# e3_tp1_ej1.net
KiCad netlist of a schematic drawn in Altium Designer
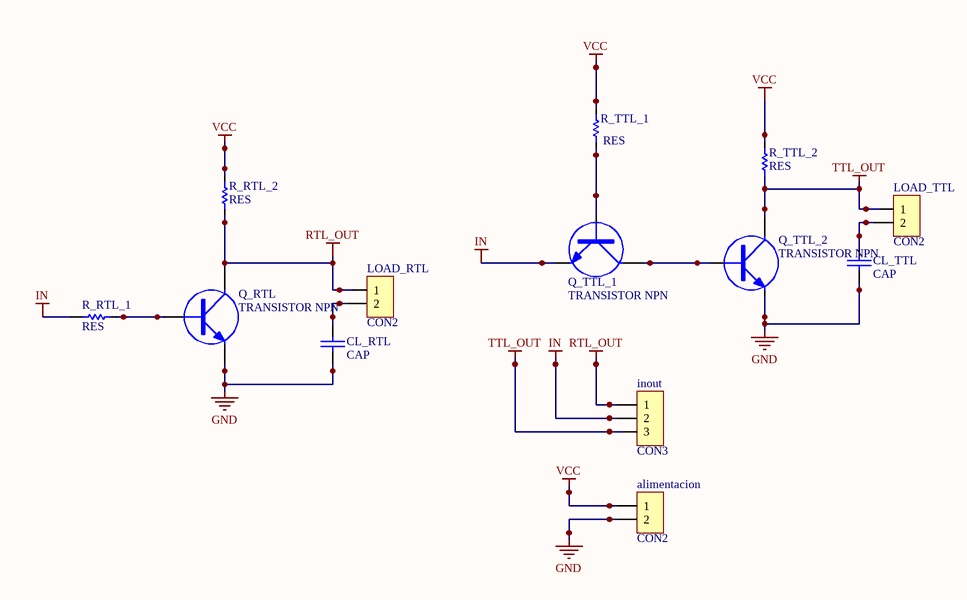
[diagram p0: e3_tp1_ej1.SchDoc]

(export (version "E")
  (design (tool "Eeschema 10.0.6"))
  (components
    (comp (ref "alimentacion") (value "CON2") (footprint "SIP2") (libsource (lib "LIBEBAL") (part "CON2")))
    (comp (ref "CL_RTL") (value "CAP") (footprint "CAP200") (libsource (lib "LIBEBAL") (part "CAP")))
    (comp (ref "CL_TTL") (value "CAP") (footprint "CAP200") (libsource (lib "LIBEBAL") (part "CAP")))
    (comp (ref "inout") (value "CON3") (footprint "SIP3") (libsource (lib "LIBEBAL") (part "CON3")))
    (comp (ref "LOAD_RTL") (value "CON2") (footprint "SIP2") (libsource (lib "LIBEBAL") (part "CON2")))
    (comp (ref "LOAD_TTL") (value "CON2") (footprint "SIP2") (libsource (lib "LIBEBAL") (part "CON2")))
    (comp (ref "Q_RTL")
      (value "TRANSISTOR NPN")
      (footprint "TO92")
      (libsource (lib "LIBEBAL") (part "TRANSISTOR NPN"))
    )
    (comp (ref "Q_TTL_1")
      (value "TRANSISTOR NPN")
      (footprint "TO92")
      (libsource (lib "LIBEBAL") (part "TRANSISTOR NPN"))
    )
    (comp (ref "Q_TTL_2")
      (value "TRANSISTOR NPN")
      (footprint "TO92")
      (libsource (lib "LIBEBAL") (part "TRANSISTOR NPN"))
    )
    (comp (ref "R_RTL_1") (value "RES") (footprint "RES300") (libsource (lib "LIBEBAL") (part "RES")))
    (comp (ref "R_RTL_2") (value "RES") (footprint "RES300") (libsource (lib "LIBEBAL") (part "RES")))
    (comp (ref "R_TTL_1") (value "RES") (footprint "RES300") (libsource (lib "LIBEBAL") (part "RES")))
    (comp (ref "R_TTL_2") (value "RES") (footprint "RES300") (libsource (lib "LIBEBAL") (part "RES")))
  )
  (nets
    (net (code "1") (name "GND") (class "Default")
      (node (ref "CL_RTL") (pin "2") (pinfunction "2_2") (pintype "passive"))
      (node (ref "CL_TTL") (pin "2") (pinfunction "2_2") (pintype "passive"))
      (node (ref "Q_RTL") (pin "3") (pinfunction "E_3") (pintype "passive"))
      (node (ref "Q_TTL_2") (pin "3") (pinfunction "E_3") (pintype "passive"))
      (node (ref "alimentacion") (pin "2") (pinfunction "2_2") (pintype "passive"))
    )
    (net (code "2") (name "IN") (class "Default")
      (node (ref "Q_TTL_1") (pin "3") (pinfunction "E_3") (pintype "passive"))
      (node (ref "R_RTL_1") (pin "1") (pinfunction "1_1") (pintype "passive"))
      (node (ref "inout") (pin "2") (pinfunction "2_2") (pintype "passive"))
    )
    (net (code "3") (name "Net-(CL_RTL-Pad1)") (class "Default")
      (node (ref "CL_RTL") (pin "1") (pinfunction "1_1") (pintype "passive"))
      (node (ref "LOAD_RTL") (pin "2") (pinfunction "2_2") (pintype "passive"))
    )
    (net (code "4") (name "Net-(CL_TTL-Pad1)") (class "Default")
      (node (ref "CL_TTL") (pin "1") (pinfunction "1_1") (pintype "passive"))
      (node (ref "LOAD_TTL") (pin "2") (pinfunction "2_2") (pintype "passive"))
    )
    (net (code "5") (name "Net-(Q_RTL-B)") (class "Default")
      (node (ref "Q_RTL") (pin "1") (pinfunction "B_1") (pintype "passive"))
      (node (ref "R_RTL_1") (pin "2") (pinfunction "2_2") (pintype "passive"))
    )
    (net (code "6") (name "Net-(Q_TTL_1-B)") (class "Default")
      (node (ref "Q_TTL_1") (pin "1") (pinfunction "B_1") (pintype "passive"))
      (node (ref "R_TTL_1") (pin "1") (pinfunction "1_1") (pintype "passive"))
    )
    (net (code "7") (name "Net-(Q_TTL_1-C)") (class "Default")
      (node (ref "Q_TTL_1") (pin "2") (pinfunction "C_2") (pintype "passive"))
      (node (ref "Q_TTL_2") (pin "1") (pinfunction "B_1") (pintype "passive"))
    )
    (net (code "8") (name "RTL_OUT") (class "Default")
      (node (ref "LOAD_RTL") (pin "1") (pinfunction "1_1") (pintype "passive"))
      (node (ref "Q_RTL") (pin "2") (pinfunction "C_2") (pintype "passive"))
      (node (ref "R_RTL_2") (pin "1") (pinfunction "1_1") (pintype "passive"))
      (node (ref "inout") (pin "1") (pinfunction "1_1") (pintype "passive"))
    )
    (net (code "9") (name "TTL_OUT") (class "Default")
      (node (ref "LOAD_TTL") (pin "1") (pinfunction "1_1") (pintype "passive"))
      (node (ref "Q_TTL_2") (pin "2") (pinfunction "C_2") (pintype "passive"))
      (node (ref "R_TTL_2") (pin "1") (pinfunction "1_1") (pintype "passive"))
      (node (ref "inout") (pin "3") (pinfunction "3_3") (pintype "passive"))
    )
    (net (code "10") (name "VCC") (class "Default")
      (node (ref "R_RTL_2") (pin "2") (pinfunction "2_2") (pintype "passive"))
      (node (ref "R_TTL_1") (pin "2") (pinfunction "2_2") (pintype "passive"))
      (node (ref "R_TTL_2") (pin "2") (pinfunction "2_2") (pintype "passive"))
      (node (ref "alimentacion") (pin "1") (pinfunction "1_1") (pintype "passive"))
    )
  )
)
